# rev1.net
KiCad netlist of a schematic drawn in EAGLE
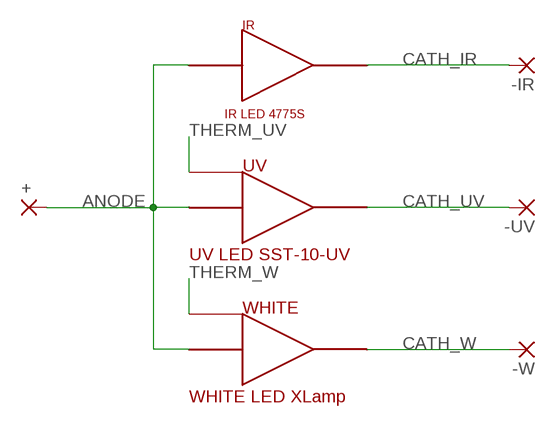
[diagram p0: schematic, sheet 1]

(export (version "E")
  (design (tool "Eeschema 10.0.6"))
  (components
    (comp (ref "+")
      (value "SMD5")
      (footprint "eagle-import:SMD2,54-5,08")
      (libsource (lib "eagle-import") (part "SMD5"))
    )
    (comp (ref "-IR")
      (value "SMD5")
      (footprint "eagle-import:SMD2,54-5,08")
      (libsource (lib "eagle-import") (part "SMD5"))
    )
    (comp (ref "-UV")
      (value "SMD5")
      (footprint "eagle-import:SMD2,54-5,08")
      (libsource (lib "eagle-import") (part "SMD5"))
    )
    (comp (ref "-W")
      (value "SMD5")
      (footprint "eagle-import:SMD2,54-5,08")
      (libsource (lib "eagle-import") (part "SMD5"))
    )
    (comp (ref "IR")
      (value "4775S")
      (footprint "eagle-import:4775S")
      (libsource (lib "eagle-import") (part "4775S"))
    )
    (comp (ref "UV")
      (value "SST-10-UV")
      (footprint "eagle-import:LED")
      (libsource (lib "eagle-import") (part "SST-10-UV"))
    )
    (comp (ref "WHITE")
      (value "XLAMPXPG2")
      (footprint "eagle-import:LED")
      (libsource (lib "eagle-import") (part "XLAMPXPG2"))
    )
  )
  (nets
    (net (code "1") (name "/ANODE") (class "Default")
      (node (ref "+") (pin "1") (pinfunction "P_1") (pintype "passive"))
      (node (ref "IR") (pin "ANODE") (pinfunction "ANODE_ANODE") (pintype "bidirectional"))
      (node (ref "IR") (pin "ANODE1") (pinfunction "ANODE_ANODE1") (pintype "bidirectional"))
      (node (ref "IR") (pin "ANODE2") (pinfunction "ANODE_ANODE2") (pintype "bidirectional"))
      (node (ref "UV") (pin "ANODE") (pinfunction "ANODE_ANODE") (pintype "bidirectional"))
      (node (ref "WHITE") (pin "ANODE") (pinfunction "ANODE_ANODE") (pintype "bidirectional"))
    )
    (net (code "2") (name "/CATH_IR") (class "Default")
      (node (ref "-IR") (pin "1") (pinfunction "P_1") (pintype "passive"))
      (node (ref "IR") (pin "CATHODE") (pinfunction "CATHODE_CATHODE") (pintype "bidirectional"))
      (node (ref "IR") (pin "CATHODE1") (pinfunction "CATHODE_CATHODE1") (pintype "bidirectional"))
    )
    (net (code "3") (name "/CATH_UV") (class "Default")
      (node (ref "-UV") (pin "1") (pinfunction "P_1") (pintype "passive"))
      (node (ref "UV") (pin "CATHODE") (pinfunction "CATHODE_CATHODE") (pintype "bidirectional"))
    )
    (net (code "4") (name "/CATH_W") (class "Default")
      (node (ref "-W") (pin "1") (pinfunction "P_1") (pintype "passive"))
      (node (ref "WHITE") (pin "CATHODE") (pinfunction "CATHODE_CATHODE") (pintype "bidirectional"))
    )
    (net (code "7") (name "/THERM_UV") (class "Default")
      (node (ref "UV") (pin "THERM") (pinfunction "THERM_THERM") (pintype "no_connect"))
    )
    (net (code "8") (name "/THERM_W") (class "Default")
      (node (ref "WHITE") (pin "THERM") (pinfunction "THERM_THERM") (pintype "no_connect"))
    )
  )
)
